# interface.net
KiCad netlist of a schematic drawn in Altium Designer
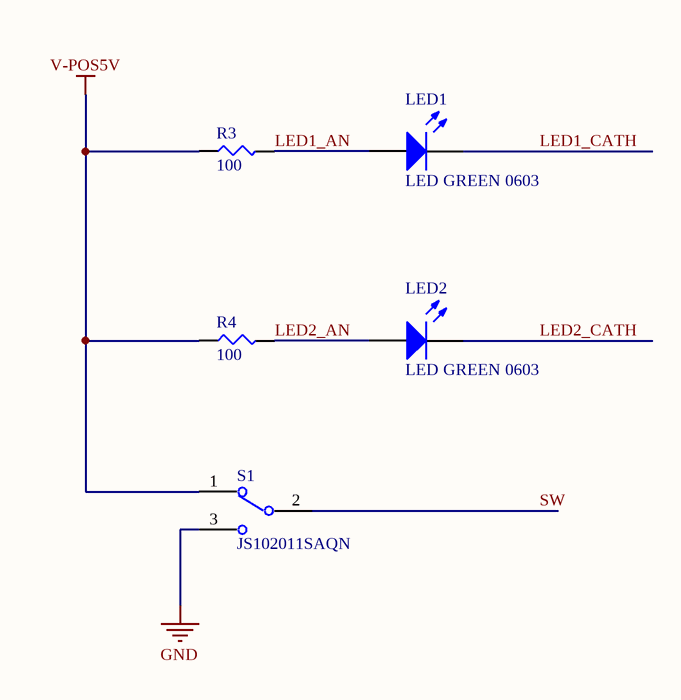
[diagram p0: interface.SchDoc]

(export (version "E")
  (design (tool "Eeschema 10.0.6"))
  (components
    (comp (ref "LED1")
      (value "LED GREEN 0603")
      (footprint "LED 0603 GREEN")
      (fields (field (name "MANUFACTURER") "Lite-On Inc."))
      (libsource (lib "firmware_tutorial_board") (part "LED GREEN 0603"))
    )
    (comp (ref "LED2")
      (value "LED GREEN 0603")
      (footprint "LED 0603 GREEN")
      (fields (field (name "MANUFACTURER") "Lite-On Inc."))
      (libsource (lib "firmware_tutorial_board") (part "LED GREEN 0603"))
    )
    (comp (ref "R3")
      (value "100")
      (footprint "SMD-0805-RES")
      (description "RES SMD 100 OHM 1% 1/8W 0805")
      (fields (field (name "PART NUMBER") "ERJ-6ENF1000V") (field (name "DIGI-KEY PART NUMBER") "P100CCT-ND"))
      (libsource (lib "firmware_tutorial_board") (part "ERJ-6ENF1000V"))
    )
    (comp (ref "R4")
      (value "100")
      (footprint "SMD-0805-RES")
      (description "RES SMD 100 OHM 1% 1/8W 0805")
      (fields (field (name "PART NUMBER") "ERJ-6ENF1000V") (field (name "DIGI-KEY PART NUMBER") "P100CCT-ND"))
      (libsource (lib "firmware_tutorial_board") (part "ERJ-6ENF1000V"))
    )
    (comp (ref "S1")
      (value "JS102011SAQN")
      (footprint "SW_JS102011SAQN")
      (description "Slide Switch SPDT Surface Mount, Right Angle")
      (fields (field (name "MF") "C&K"))
      (libsource (lib "firmware_tutorial_board") (part "JS102011SAQN"))
    )
  )
  (nets
    (net (code "1") (name "/LED1_AN") (class "Default")
      (node (ref "LED1") (pin "1") (pinfunction "A_1") (pintype "passive"))
      (node (ref "R3") (pin "2") (pinfunction "2_2") (pintype "passive"))
    )
    (net (code "2") (name "/LED1_CATH") (class "Default")
      (node (ref "LED1") (pin "2") (pinfunction "K_2") (pintype "passive"))
    )
    (net (code "3") (name "/LED2_AN") (class "Default")
      (node (ref "LED2") (pin "1") (pinfunction "A_1") (pintype "passive"))
      (node (ref "R4") (pin "2") (pinfunction "2_2") (pintype "passive"))
    )
    (net (code "4") (name "/LED2_CATH") (class "Default")
      (node (ref "LED2") (pin "2") (pinfunction "K_2") (pintype "passive"))
    )
    (net (code "5") (name "/SW") (class "Default")
      (node (ref "S1") (pin "2") (pinfunction "2_2") (pintype "passive"))
    )
    (net (code "6") (name "GND") (class "Default")
      (node (ref "S1") (pin "3") (pinfunction "3_3") (pintype "passive"))
    )
    (net (code "7") (name "V-POS5V") (class "Default")
      (node (ref "R3") (pin "1") (pinfunction "1_1") (pintype "passive"))
      (node (ref "R4") (pin "1") (pinfunction "1_1") (pintype "passive"))
      (node (ref "S1") (pin "1") (pinfunction "1_1") (pintype "passive"))
    )
  )
)
